# DC-DC.net
KiCad netlist of a schematic drawn in Altium Designer
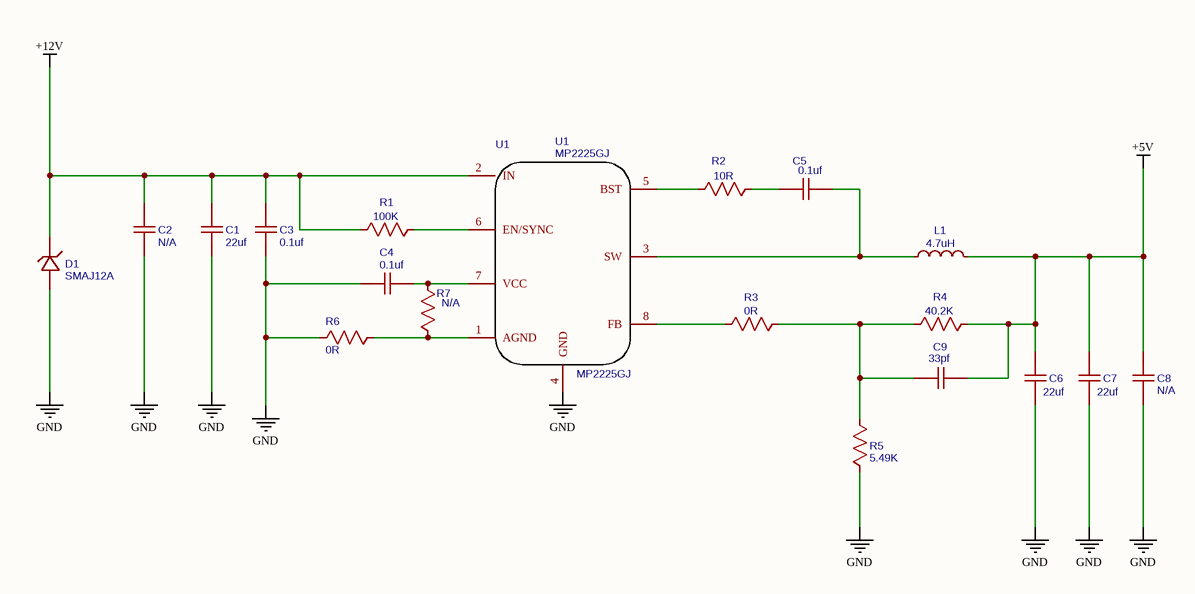
[diagram p0: DC-DC.SchDoc]

(export (version "E")
  (design (tool "Eeschema 10.0.6"))
  (components
    (comp (ref "C1")
      (value "22uf")
      (footprint "C1206")
      (fields (field (name "CONTRIBUTOR") "LCEDA_Lib"))
      (libsource (lib "altium-import") (part "root_1_22uf_"))
    )
    (comp (ref "C2")
      (value "N/A")
      (footprint "C1206")
      (fields (field (name "CONTRIBUTOR") "LCEDA_Lib"))
      (libsource (lib "altium-import") (part "root_1_N/A_"))
    )
    (comp (ref "C3")
      (value "0.1uf")
      (footprint "C0603")
      (fields (field (name "CONTRIBUTOR") "LCEDA_Lib"))
      (libsource (lib "altium-import") (part "root_1_0.1uf_"))
    )
    (comp (ref "C4")
      (value "0.1uf")
      (footprint "C0603")
      (fields (field (name "CONTRIBUTOR") "LCEDA_Lib"))
      (libsource (lib "altium-import") (part "root_0_0.1uf_"))
    )
    (comp (ref "C5")
      (value "0.1uf")
      (footprint "C0603")
      (fields (field (name "CONTRIBUTOR") "LCEDA_Lib"))
      (libsource (lib "altium-import") (part "root_0_0.1uf_"))
    )
    (comp (ref "C6")
      (value "22uf")
      (footprint "C0805")
      (fields (field (name "CONTRIBUTOR") "LCEDA_Lib"))
      (libsource (lib "altium-import") (part "root_1_22uf_"))
    )
    (comp (ref "C7")
      (value "22uf")
      (footprint "C0805")
      (fields (field (name "CONTRIBUTOR") "LCEDA_Lib"))
      (libsource (lib "altium-import") (part "root_1_22uf_"))
    )
    (comp (ref "C8")
      (value "N/A")
      (footprint "C0805")
      (fields (field (name "CONTRIBUTOR") "LCEDA_Lib"))
      (libsource (lib "altium-import") (part "root_1_N/A_"))
    )
    (comp (ref "C9")
      (value "33pf")
      (footprint "C0603")
      (fields (field (name "CONTRIBUTOR") "LCEDA_Lib"))
      (libsource (lib "altium-import") (part "root_0_33pf_"))
    )
    (comp (ref "D1")
      (value "SMAJ12A")
      (footprint "SMA_L4.4-W2.8-LS5.4-RD")
      (fields
        (field (name "BOM_SUPPLIER PART") "C309908")
        (field (name "BOM_MANUFACTURER PART") "SMAJ70A")
        (field (name "CONTRIBUTOR") "LCSC")
      )
      (libsource (lib "altium-import") (part "root_3_SMAJ12A_"))
    )
    (comp (ref "L1")
      (value "4.7uH")
      (footprint "IND-SMD_L7.8-W7.0_MAPM0630F")
      (fields
        (field (name "BOM_SUPPLIER PART") "C334085")
        (field (name "BOM_MANUFACTURER PART") "JSHC0630H-150M-G")
        (field (name "CONTRIBUTOR") "LCSC")
      )
      (libsource (lib "altium-import") (part "root_0_4.7uH_"))
    )
    (comp (ref "R1")
      (value "100K")
      (footprint "R0603")
      (fields (field (name "CONTRIBUTOR") "LCEDA_Lib"))
      (libsource (lib "altium-import") (part "root_0_100K_"))
    )
    (comp (ref "R2")
      (value "10R")
      (footprint "R0603")
      (fields (field (name "CONTRIBUTOR") "LCEDA_Lib"))
      (libsource (lib "altium-import") (part "root_0_10R_"))
    )
    (comp (ref "R3")
      (value "0R")
      (footprint "R0603")
      (fields (field (name "CONTRIBUTOR") "LCEDA_Lib"))
      (libsource (lib "altium-import") (part "root_0_0R_"))
    )
    (comp (ref "R4")
      (value "40.2K")
      (footprint "R0603")
      (fields (field (name "CONTRIBUTOR") "LCEDA_Lib"))
      (libsource (lib "altium-import") (part "root_0_40.2K_"))
    )
    (comp (ref "R5")
      (value "5.49K")
      (footprint "R0603")
      (fields (field (name "CONTRIBUTOR") "LCEDA_Lib"))
      (libsource (lib "altium-import") (part "root_1_5.49K_"))
    )
    (comp (ref "R6")
      (value "0R")
      (footprint "R0603")
      (fields (field (name "CONTRIBUTOR") "LCEDA_Lib"))
      (libsource (lib "altium-import") (part "root_0_100K_"))
    )
    (comp (ref "R7")
      (value "N/A")
      (footprint "R0603")
      (fields (field (name "CONTRIBUTOR") "LCEDA_Lib"))
      (libsource (lib "altium-import") (part "root_3_100K_"))
    )
    (comp (ref "U1")
      (value "MP2225GJ")
      (footprint "TSOT23-8")
      (fields (field (name "CONTRIBUTOR") "sunhaoqin"))
      (libsource (lib "altium-import") (part "root_0_MP2225GJ_"))
    )
  )
  (nets
    (net (code "1") (name "+5V") (class "Default")
      (node (ref "C6") (pin "2") (pinfunction "2_2") (pintype "passive"))
      (node (ref "C7") (pin "2") (pinfunction "2_2") (pintype "passive"))
      (node (ref "C8") (pin "2") (pinfunction "2_2") (pintype "passive"))
      (node (ref "C9") (pin "2") (pinfunction "2_2") (pintype "passive"))
      (node (ref "L1") (pin "2") (pinfunction "2_2") (pintype "passive"))
      (node (ref "R4") (pin "2") (pinfunction "2_2") (pintype "passive"))
    )
    (net (code "2") (name "+12V") (class "Default")
      (node (ref "C1") (pin "2") (pinfunction "2_2") (pintype "passive"))
      (node (ref "C2") (pin "2") (pinfunction "2_2") (pintype "passive"))
      (node (ref "C3") (pin "2") (pinfunction "2_2") (pintype "passive"))
      (node (ref "D1") (pin "1") (pinfunction "1_1") (pintype "passive"))
      (node (ref "R1") (pin "1") (pinfunction "1_1") (pintype "passive"))
      (node (ref "U1") (pin "2") (pinfunction "IN_2") (pintype "passive"))
    )
    (net (code "3") (name "GND") (class "Default")
      (node (ref "C1") (pin "1") (pinfunction "1_1") (pintype "passive"))
      (node (ref "C2") (pin "1") (pinfunction "1_1") (pintype "passive"))
      (node (ref "C3") (pin "1") (pinfunction "1_1") (pintype "passive"))
      (node (ref "C4") (pin "1") (pinfunction "1_1") (pintype "passive"))
      (node (ref "C6") (pin "1") (pinfunction "1_1") (pintype "passive"))
      (node (ref "C7") (pin "1") (pinfunction "1_1") (pintype "passive"))
      (node (ref "C8") (pin "1") (pinfunction "1_1") (pintype "passive"))
      (node (ref "D1") (pin "2") (pinfunction "2_2") (pintype "passive"))
      (node (ref "R5") (pin "1") (pinfunction "1_1") (pintype "passive"))
      (node (ref "R6") (pin "1") (pinfunction "1_1") (pintype "passive"))
      (node (ref "U1") (pin "4") (pinfunction "GND_4") (pintype "passive"))
    )
    (net (code "4") (name "Net-(C5-Pad1)") (class "Default")
      (node (ref "C5") (pin "1") (pinfunction "1_1") (pintype "passive"))
      (node (ref "R2") (pin "2") (pinfunction "2_2") (pintype "passive"))
    )
    (net (code "5") (name "Net-(C9-Pad1)") (class "Default")
      (node (ref "C9") (pin "1") (pinfunction "1_1") (pintype "passive"))
      (node (ref "R3") (pin "2") (pinfunction "2_2") (pintype "passive"))
      (node (ref "R4") (pin "1") (pinfunction "1_1") (pintype "passive"))
      (node (ref "R5") (pin "2") (pinfunction "2_2") (pintype "passive"))
    )
    (net (code "6") (name "Net-(U1-AGND)") (class "Default")
      (node (ref "R6") (pin "2") (pinfunction "2_2") (pintype "passive"))
      (node (ref "R7") (pin "2") (pinfunction "2_2") (pintype "passive"))
      (node (ref "U1") (pin "1") (pinfunction "AGND_1") (pintype "passive"))
    )
    (net (code "7") (name "Net-(U1-BST)") (class "Default")
      (node (ref "R2") (pin "1") (pinfunction "1_1") (pintype "passive"))
      (node (ref "U1") (pin "5") (pinfunction "BST_5") (pintype "passive"))
    )
    (net (code "8") (name "Net-(U1-EN{slash}SYNC)") (class "Default")
      (node (ref "R1") (pin "2") (pinfunction "2_2") (pintype "passive"))
      (node (ref "U1") (pin "6") (pinfunction "EN/SYNC_6") (pintype "passive"))
    )
    (net (code "9") (name "Net-(U1-FB)") (class "Default")
      (node (ref "R3") (pin "1") (pinfunction "1_1") (pintype "passive"))
      (node (ref "U1") (pin "8") (pinfunction "FB_8") (pintype "passive"))
    )
    (net (code "10") (name "Net-(U1-SW)") (class "Default")
      (node (ref "C5") (pin "2") (pinfunction "2_2") (pintype "passive"))
      (node (ref "L1") (pin "1") (pinfunction "1_1") (pintype "passive"))
      (node (ref "U1") (pin "3") (pinfunction "SW_3") (pintype "passive"))
    )
    (net (code "11") (name "Net-(U1-VCC)") (class "Default")
      (node (ref "C4") (pin "2") (pinfunction "2_2") (pintype "passive"))
      (node (ref "R7") (pin "1") (pinfunction "1_1") (pintype "passive"))
      (node (ref "U1") (pin "7") (pinfunction "VCC_7") (pintype "passive"))
    )
  )
)
